# SH3-FTDI.net
KiCad netlist of a schematic drawn in Altium Designer
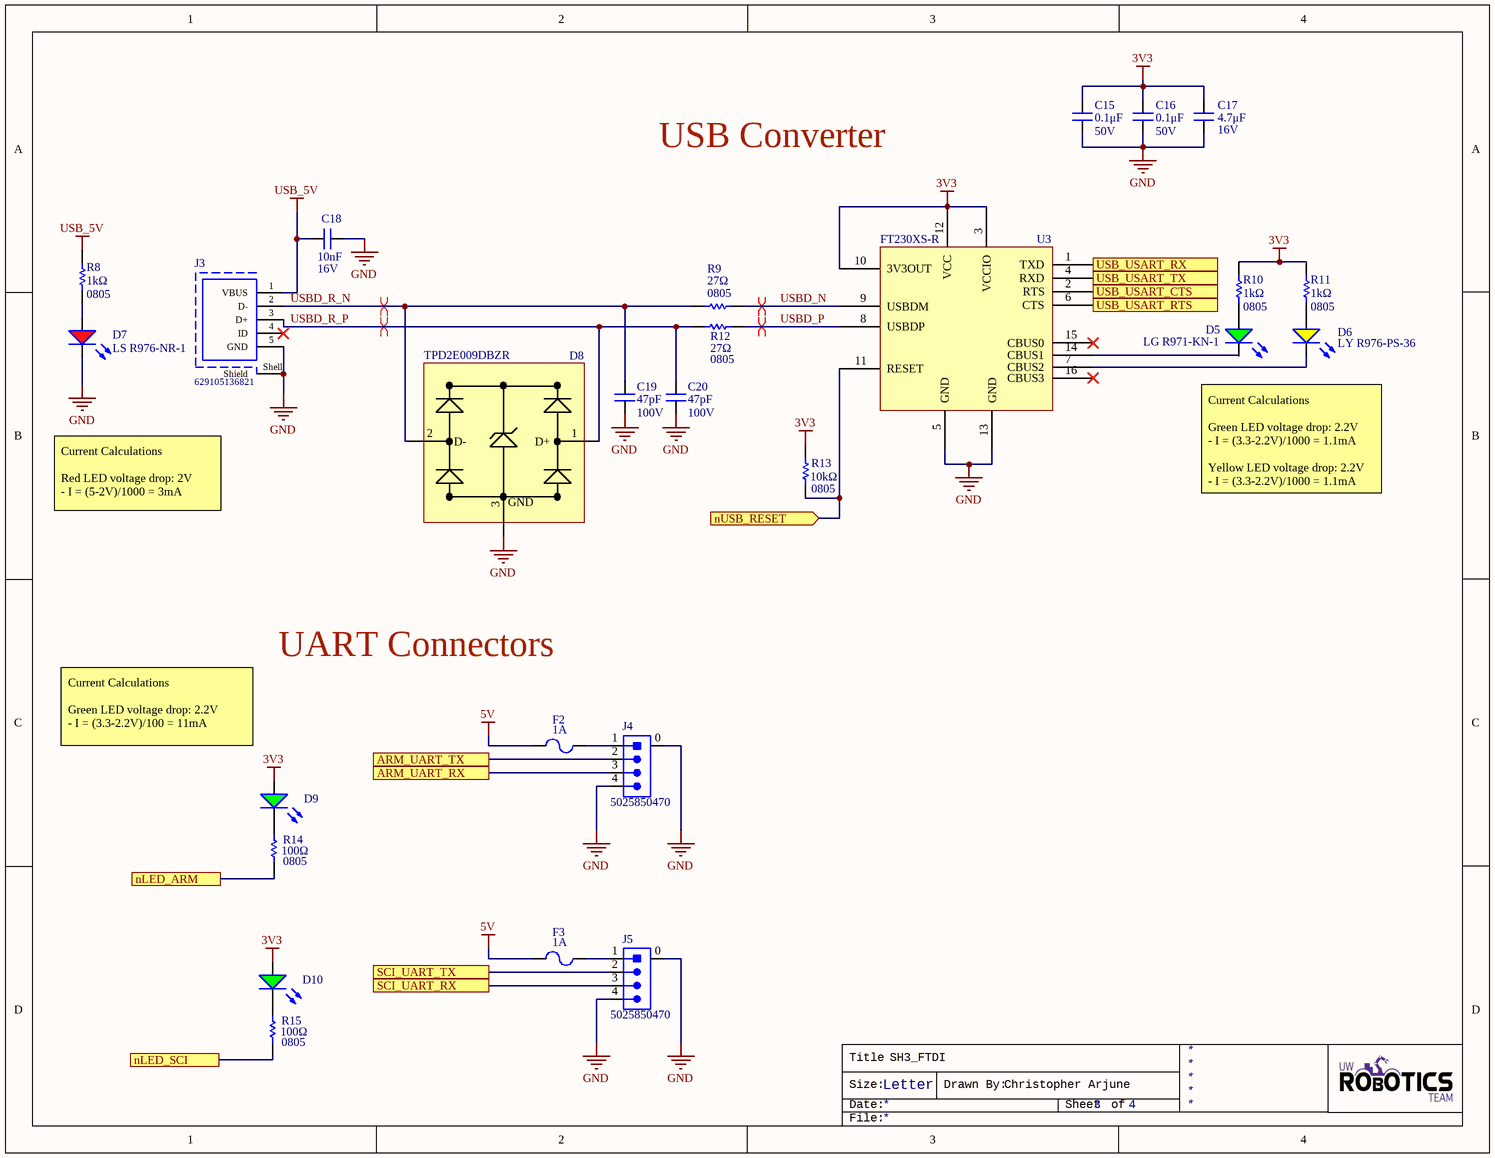
[diagram p0: SH3-FTDI.SchDoc]

(export (version "E")
  (design (tool "Eeschema 10.0.6"))
  (components
    (comp (ref "C15")
      (value "0.1μF")
      (footprint "CAPC2012X140N")
      (description "CAP CER 0.1UF 50V X7R 0805")
      (fields (field (name "TOLERANCE") "10%") (field (name "VOLTAGE RATING") "50V"))
      (libsource (lib "*") (part "CAP_0.1uF_50V_0805"))
    )
    (comp (ref "C16")
      (value "0.1μF")
      (footprint "CAPC2012X140N")
      (description "CAP CER 0.1UF 50V X7R 0805")
      (fields (field (name "TOLERANCE") "10%") (field (name "VOLTAGE RATING") "50V"))
      (libsource (lib "*") (part "CAP_0.1uF_50V_0805"))
    )
    (comp (ref "C17")
      (value "4.7μF")
      (footprint "CAPC2012X140N")
      (description "CAP CER 4.7UF 16V X5R 0805")
      (fields (field (name "TOLERANCE") "10%") (field (name "VOLTAGE RATING") "16V"))
      (libsource (lib "*") (part "CAP_4.7uF_16V_0805"))
    )
    (comp (ref "C18")
      (value "~")
      (footprint "CAPC2012X140N")
      (description "CAP CER 10000PF 16V X7R 0805")
      (fields
        (field (name "TOLERANCE") "10%")
        (field (name "CAPACITANCE") "10nF")
        (field (name "VOLTAGE RATING") "16V")
      )
      (libsource (lib "*") (part "CAP_10nF_16V_0805"))
    )
    (comp (ref "C19")
      (value "~")
      (footprint "CAPC2012X140N")
      (description "CAP CER 47PF 100V NPO 0805")
      (fields
        (field (name "TOLERANCE") "5%")
        (field (name "CAPACITANCE") "47pF")
        (field (name "VOLTAGE RATING") "100V")
      )
      (libsource (lib "*") (part "CAP_47pF_100V_0805"))
    )
    (comp (ref "C20")
      (value "~")
      (footprint "CAPC2012X140N")
      (description "CAP CER 47PF 100V NPO 0805")
      (fields
        (field (name "TOLERANCE") "5%")
        (field (name "CAPACITANCE") "47pF")
        (field (name "VOLTAGE RATING") "100V")
      )
      (libsource (lib "*") (part "CAP_47pF_100V_0805"))
    )
    (comp (ref "D5")
      (value "LG R971-KN-1")
      (footprint "LED_0805_LINE")
      (description "LED GREEN DIFFUSED 0805 SMD")
      (libsource (lib "UWRT_Schematic_Library_2020") (part "DIO_LED_G"))
    )
    (comp (ref "D6")
      (value "LY R976-PS-36")
      (footprint "LED_0805_LINE")
      (description "LED YELLOW DIFFUSED 0805 SMD")
      (libsource (lib "UWRT_Schematic_Library_2020") (part "DIO_LED_Y"))
    )
    (comp (ref "D7")
      (value "LS R976-NR-1")
      (footprint "LED_0805_LINE")
      (description "LED RED DIFFUSED 0805 SMD")
      (libsource (lib "UWRT_Schematic_Library_2020") (part "DIO_LED_R"))
    )
    (comp (ref "D8")
      (value "TVS_DIODE_USB_5.5V")
      (footprint "SOT23-3")
      (description "ESD Suppressor Diode Arrays 8KV 3-Pin SOT-23 T/R")
      (fields
        (field (name "MANUFACTURER") "Texas Instruments")
        (field (name "MANUFACTURER PART NUMBER") "TPD2E009DBZR")
      )
      (libsource (lib "UWRT_Schematic_Library_2020") (part "TVS_DIODE_USB_5.5V"))
    )
    (comp (ref "D9")
      (value "LG R971-KN-1")
      (footprint "LED_0805_LINE")
      (description "LED GREEN DIFFUSED 0805 SMD")
      (libsource (lib "UWRT_Schematic_Library_2020") (part "DIO_LED_G"))
    )
    (comp (ref "D10")
      (value "LG R971-KN-1")
      (footprint "LED_0805_LINE")
      (description "LED GREEN DIFFUSED 0805 SMD")
      (libsource (lib "UWRT_Schematic_Library_2020") (part "DIO_LED_G"))
    )
    (comp (ref "F2")
      (value "FUSE_1A_1206")
      (footprint "FUSC3215X78N")
      (description "FUSE BOARD MOUNT 1A 125VAC 63VDC")
      (fields (field (name "CURRENT RATING") "1A"))
      (libsource (lib "UWRT_Schematic_Library_2020") (part "FUSE_1A_1206"))
    )
    (comp (ref "F3")
      (value "FUSE_1A_1206")
      (footprint "FUSC3215X78N")
      (description "FUSE BOARD MOUNT 1A 125VAC 63VDC")
      (fields (field (name "CURRENT RATING") "1A"))
      (libsource (lib "UWRT_Schematic_Library_2020") (part "FUSE_1A_1206"))
    )
    (comp (ref "J3")
      (value "629105136821")
      (footprint "629105136821")
      (description "Micro USB 2.0 Type B Receptacle WR-COM, Horizontal, SMT, with Pads and Pegs")
      (fields (field (name "MANUFACTURER") "Wurth Elektronik") (field (name "PUBLISHER") "WurthElektronik"))
      (libsource (lib "Altium Content Vault") (part "WE-USB-5-1SHLD"))
    )
    (comp (ref "J4")
      (value "CON_4M_SM_RA")
      (footprint "MOLEX-5025850470")
      (description "CONN HEADER SMD RIGHT ANGLE 1.5 MM PITCH")
      (fields (field (name "MANUFACTURER") "Molex") (field (name "MANUFACTOR NUMBER") "5025850470"))
      (libsource (lib "UWRT_Schematic_Library_2020") (part "CON_4M_SM_RA"))
    )
    (comp (ref "J5")
      (value "CON_4M_SM_RA")
      (footprint "MOLEX-5025850470")
      (description "CONN HEADER SMD RIGHT ANGLE 1.5 MM PITCH")
      (fields (field (name "MANUFACTURER") "Molex") (field (name "MANUFACTOR NUMBER") "5025850470"))
      (libsource (lib "UWRT_Schematic_Library_2020") (part "CON_4M_SM_RA"))
    )
    (comp (ref "R8")
      (value "1kΩ")
      (footprint "RESC2012X60N")
      (description "RES SMD 1K OHM 1% 1/8W 0805")
      (fields (field (name "TOLERANCE") "1%") (field (name "CASE CODE (IMPERIAL)") "0805"))
      (libsource (lib "UWRT_Schematic_Library_2020") (part "RES_1kΩ_0805"))
    )
    (comp (ref "R9")
      (value "RES_27Ω_0805")
      (footprint "RESC2012X60N")
      (description "RES SMD 27 OHM 1% 1/8W 0805")
      (fields
        (field (name "TOLERANCE") "1%")
        (field (name "CASE/PACKAGE") "0805")
        (field (name "RESISTANCE") "27Ω")
      )
      (libsource (lib "UWRT_Schematic_Library_2020") (part "RES_27Ω_0805"))
    )
    (comp (ref "R10")
      (value "1kΩ")
      (footprint "RESC2012X60N")
      (description "RES SMD 1K OHM 1% 1/8W 0805")
      (fields (field (name "TOLERANCE") "1%") (field (name "CASE CODE (IMPERIAL)") "0805"))
      (libsource (lib "UWRT_Schematic_Library_2020") (part "RES_1kΩ_0805"))
    )
    (comp (ref "R11")
      (value "1kΩ")
      (footprint "RESC2012X60N")
      (description "RES SMD 1K OHM 1% 1/8W 0805")
      (fields (field (name "TOLERANCE") "1%") (field (name "CASE CODE (IMPERIAL)") "0805"))
      (libsource (lib "UWRT_Schematic_Library_2020") (part "RES_1kΩ_0805"))
    )
    (comp (ref "R12")
      (value "RES_27Ω_0805")
      (footprint "RESC2012X60N")
      (description "RES SMD 27 OHM 1% 1/8W 0805")
      (fields
        (field (name "TOLERANCE") "1%")
        (field (name "CASE/PACKAGE") "0805")
        (field (name "RESISTANCE") "27Ω")
      )
      (libsource (lib "UWRT_Schematic_Library_2020") (part "RES_27Ω_0805"))
    )
    (comp (ref "R13")
      (value "10kΩ")
      (footprint "RESC2012X60N")
      (description "RES SMD 10K OHM 1% 1/8W 0805")
      (fields
        (field (name "TOLERANCE") "1%")
        (field (name "CASE CODE (IMPERIAL)") "0805")
        (field (name "Comment") "RES_10kΩ_0805")
      )
      (libsource (lib "UWRT_Schematic_Library_2020") (part "RES_10kΩ_0805"))
    )
    (comp (ref "R14")
      (value "100Ω")
      (footprint "RESC2012X60N")
      (description "RES SMD 100 OHM 1% 1/8W 0805")
      (fields (field (name "CASE CODE (IMPERIAL)") "0805") (field (name "Comment") "RES_100Ω_0805"))
      (libsource (lib "UWRT_Schematic_Library_2020") (part "RES_100Ω_0805"))
    )
    (comp (ref "R15")
      (value "100Ω")
      (footprint "RESC2012X60N")
      (description "RES SMD 100 OHM 1% 1/8W 0805")
      (fields (field (name "CASE CODE (IMPERIAL)") "0805") (field (name "Comment") "RES_100Ω_0805"))
      (libsource (lib "UWRT_Schematic_Library_2020") (part "RES_100Ω_0805"))
    )
    (comp (ref "U3")
      (value "IC_USB_TRANSCEIVER")
      (footprint "SSOP16-0.635-5X4MM")
      (fields (field (name "MANUFACTURER PART NUMBER 1") "FT230XS-R"))
      (libsource (lib "UWRT_Schematic_Library_2020") (part "IC_USB_TRANSCEIVER"))
    )
  )
  (nets
    (net (code "1") (name "/ARM_UART_RX") (class "Default")
      (node (ref "J4") (pin "3") (pinfunction "3_3") (pintype "passive"))
    )
    (net (code "2") (name "/ARM_UART_TX") (class "Default")
      (node (ref "J4") (pin "2") (pinfunction "2_2") (pintype "passive"))
    )
    (net (code "3") (name "/SCI_UART_RX") (class "Default")
      (node (ref "J5") (pin "3") (pinfunction "3_3") (pintype "passive"))
    )
    (net (code "4") (name "/SCI_UART_TX") (class "Default")
      (node (ref "J5") (pin "2") (pinfunction "2_2") (pintype "passive"))
    )
    (net (code "5") (name "/USBD_N") (class "Default")
      (node (ref "R9") (pin "2") (pinfunction "2_2") (pintype "passive"))
      (node (ref "U3") (pin "9") (pinfunction "USBDM_9") (pintype "passive"))
    )
    (net (code "6") (name "/USBD_P") (class "Default")
      (node (ref "R12") (pin "2") (pinfunction "2_2") (pintype "passive"))
      (node (ref "U3") (pin "8") (pinfunction "USBDP_8") (pintype "passive"))
    )
    (net (code "7") (name "/USBD_R_N") (class "Default")
      (node (ref "C19") (pin "1") (pinfunction "1_1") (pintype "passive"))
      (node (ref "D8") (pin "2") (pinfunction "D-_2") (pintype "passive"))
      (node (ref "J3") (pin "2") (pinfunction "D-_2") (pintype "passive"))
      (node (ref "R9") (pin "1") (pinfunction "1_1") (pintype "passive"))
    )
    (net (code "8") (name "/USBD_R_P") (class "Default")
      (node (ref "C20") (pin "1") (pinfunction "1_1") (pintype "passive"))
      (node (ref "D8") (pin "1") (pinfunction "D+_1") (pintype "passive"))
      (node (ref "J3") (pin "3") (pinfunction "D+_3") (pintype "passive"))
      (node (ref "R12") (pin "1") (pinfunction "1_1") (pintype "passive"))
    )
    (net (code "9") (name "/USB_USART_CTS") (class "Default")
      (node (ref "U3") (pin "2") (pinfunction "RTS_2") (pintype "passive"))
    )
    (net (code "10") (name "/USB_USART_RTS") (class "Default")
      (node (ref "U3") (pin "6") (pinfunction "CTS_6") (pintype "passive"))
    )
    (net (code "11") (name "/USB_USART_RX") (class "Default")
      (node (ref "U3") (pin "1") (pinfunction "TXD_1") (pintype "passive"))
    )
    (net (code "12") (name "/USB_USART_TX") (class "Default")
      (node (ref "U3") (pin "4") (pinfunction "RXD_4") (pintype "passive"))
    )
    (net (code "13") (name "/nLED_ARM") (class "Default")
      (node (ref "R14") (pin "1") (pinfunction "1_1") (pintype "passive"))
    )
    (net (code "14") (name "/nLED_SCI") (class "Default")
      (node (ref "R15") (pin "1") (pinfunction "1_1") (pintype "passive"))
    )
    (net (code "15") (name "/nUSB_RESET") (class "Default")
      (node (ref "R13") (pin "1") (pinfunction "1_1") (pintype "passive"))
      (node (ref "U3") (pin "11") (pinfunction "RESET_11") (pintype "passive"))
    )
    (net (code "16") (name "3V3") (class "Default")
      (node (ref "C15") (pin "2") (pinfunction "2_2") (pintype "passive"))
      (node (ref "C16") (pin "2") (pinfunction "2_2") (pintype "passive"))
      (node (ref "C17") (pin "2") (pinfunction "2_2") (pintype "passive"))
      (node (ref "D10") (pin "1") (pinfunction "A_1") (pintype "passive"))
      (node (ref "D9") (pin "1") (pinfunction "A_1") (pintype "passive"))
      (node (ref "R10") (pin "2") (pinfunction "2_2") (pintype "passive"))
      (node (ref "R11") (pin "2") (pinfunction "2_2") (pintype "passive"))
      (node (ref "R13") (pin "2") (pinfunction "2_2") (pintype "passive"))
      (node (ref "U3") (pin "10") (pinfunction "3V3OUT_10") (pintype "passive"))
      (node (ref "U3") (pin "12") (pinfunction "VCC_12") (pintype "passive"))
      (node (ref "U3") (pin "3") (pinfunction "VCCIO_3") (pintype "passive"))
    )
    (net (code "17") (name "5V") (class "Default")
      (node (ref "F2") (pin "1") (pinfunction "1_1") (pintype "passive"))
      (node (ref "F3") (pin "1") (pinfunction "1_1") (pintype "passive"))
    )
    (net (code "18") (name "GND") (class "Default")
      (node (ref "C15") (pin "1") (pinfunction "1_1") (pintype "passive"))
      (node (ref "C16") (pin "1") (pinfunction "1_1") (pintype "passive"))
      (node (ref "C17") (pin "1") (pinfunction "1_1") (pintype "passive"))
      (node (ref "C18") (pin "2") (pinfunction "2_2") (pintype "passive"))
      (node (ref "C19") (pin "2") (pinfunction "2_2") (pintype "passive"))
      (node (ref "C20") (pin "2") (pinfunction "2_2") (pintype "passive"))
      (node (ref "D7") (pin "2") (pinfunction "K_2") (pintype "passive"))
      (node (ref "D8") (pin "3") (pinfunction "GND_3") (pintype "passive"))
      (node (ref "J3") (pin "5") (pinfunction "GND_5") (pintype "passive"))
      (node (ref "J3") (pin "Shell") (pinfunction "Shield_Shell") (pintype "passive"))
      (node (ref "J4") (pin "0") (pinfunction "0_0") (pintype "passive"))
      (node (ref "J4") (pin "4") (pinfunction "4_4") (pintype "passive"))
      (node (ref "J5") (pin "0") (pinfunction "0_0") (pintype "passive"))
      (node (ref "J5") (pin "4") (pinfunction "4_4") (pintype "passive"))
      (node (ref "U3") (pin "13") (pinfunction "GND_13") (pintype "passive"))
      (node (ref "U3") (pin "5") (pinfunction "GND_5") (pintype "passive"))
    )
    (net (code "19") (name "Net-(D5-A)") (class "Default")
      (node (ref "D5") (pin "1") (pinfunction "A_1") (pintype "passive"))
      (node (ref "R10") (pin "1") (pinfunction "1_1") (pintype "passive"))
    )
    (net (code "20") (name "Net-(D5-K)") (class "Default")
      (node (ref "D5") (pin "2") (pinfunction "K_2") (pintype "passive"))
      (node (ref "U3") (pin "14") (pinfunction "CBUS1_14") (pintype "passive"))
    )
    (net (code "21") (name "Net-(D6-A)") (class "Default")
      (node (ref "D6") (pin "1") (pinfunction "A_1") (pintype "passive"))
      (node (ref "R11") (pin "1") (pinfunction "1_1") (pintype "passive"))
    )
    (net (code "22") (name "Net-(D6-K)") (class "Default")
      (node (ref "D6") (pin "2") (pinfunction "K_2") (pintype "passive"))
      (node (ref "U3") (pin "7") (pinfunction "CBUS2_7") (pintype "passive"))
    )
    (net (code "23") (name "Net-(D7-A)") (class "Default")
      (node (ref "D7") (pin "1") (pinfunction "A_1") (pintype "passive"))
      (node (ref "R8") (pin "1") (pinfunction "1_1") (pintype "passive"))
    )
    (net (code "24") (name "Net-(D9-K)") (class "Default")
      (node (ref "D9") (pin "2") (pinfunction "K_2") (pintype "passive"))
      (node (ref "R14") (pin "2") (pinfunction "2_2") (pintype "passive"))
    )
    (net (code "25") (name "Net-(D10-K)") (class "Default")
      (node (ref "D10") (pin "2") (pinfunction "K_2") (pintype "passive"))
      (node (ref "R15") (pin "2") (pinfunction "2_2") (pintype "passive"))
    )
    (net (code "26") (name "Net-(F2-Pad2)") (class "Default")
      (node (ref "F2") (pin "2") (pinfunction "2_2") (pintype "passive"))
      (node (ref "J4") (pin "1") (pinfunction "1_1") (pintype "passive"))
    )
    (net (code "27") (name "Net-(F3-Pad2)") (class "Default")
      (node (ref "F3") (pin "2") (pinfunction "2_2") (pintype "passive"))
      (node (ref "J5") (pin "1") (pinfunction "1_1") (pintype "passive"))
    )
    (net (code "28") (name "USB_5V") (class "Default")
      (node (ref "C18") (pin "1") (pinfunction "1_1") (pintype "passive"))
      (node (ref "J3") (pin "1") (pinfunction "VBUS_1") (pintype "passive"))
      (node (ref "R8") (pin "2") (pinfunction "2_2") (pintype "passive"))
    )
    (net (code "29") (name "unconnected-(J3-ID-Pad4)") (class "Default")
      (node (ref "J3") (pin "4") (pinfunction "ID_4") (pintype "passive+no_connect"))
    )
    (net (code "30") (name "unconnected-(U3-CBUS0-Pad15)") (class "Default")
      (node (ref "U3") (pin "15") (pinfunction "CBUS0_15") (pintype "passive+no_connect"))
    )
    (net (code "31") (name "unconnected-(U3-CBUS3-Pad16)") (class "Default")
      (node (ref "U3") (pin "16") (pinfunction "CBUS3_16") (pintype "passive+no_connect"))
    )
  )
)
